# RGB.net
KiCad netlist of a schematic drawn in EAGLE
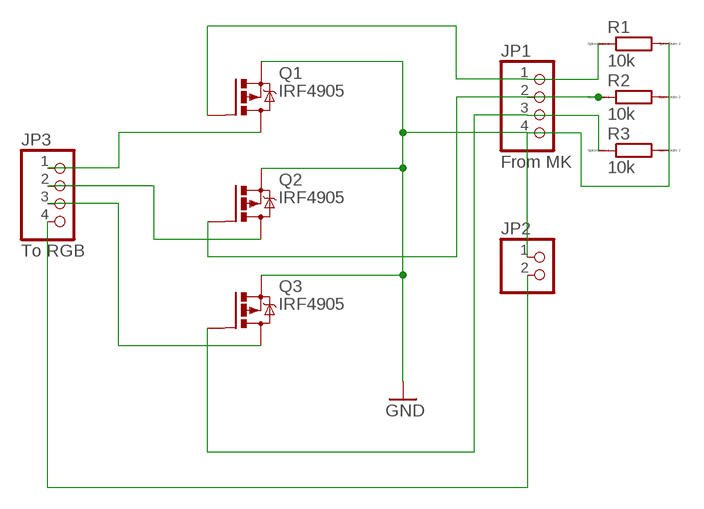
[diagram p0: schematic, sheet 1]

(export (version "E")
  (design (tool "Eeschema 10.0.6"))
  (components
    (comp (ref "JP1")
      (value "From MK")
      (footprint "eagle-import:1X04_90")
      (libsource (lib "eagle-import") (part "PINHD-1X4/90"))
    )
    (comp (ref "JP2")
      (value "PINHD-1X2/90")
      (footprint "eagle-import:1X02_90")
      (libsource (lib "eagle-import") (part "PINHD-1X2/90"))
    )
    (comp (ref "JP3")
      (value "To RGB")
      (footprint "eagle-import:1X04_90")
      (libsource (lib "eagle-import") (part "PINHD-1X4/90"))
    )
    (comp (ref "Q1")
      (value "IRF4905")
      (footprint "eagle-import:TO220BH")
      (libsource (lib "eagle-import") (part "IRF4905"))
    )
    (comp (ref "Q2")
      (value "IRF4905")
      (footprint "eagle-import:TO220BH")
      (libsource (lib "eagle-import") (part "IRF4905"))
    )
    (comp (ref "Q3")
      (value "IRF4905")
      (footprint "eagle-import:TO220BH")
      (libsource (lib "eagle-import") (part "IRF4905"))
    )
    (comp (ref "R1")
      (value "10k")
      (footprint "eagle-import:0207_10")
      (libsource (lib "eagle-import") (part "R0207/10"))
    )
    (comp (ref "R2")
      (value "10k")
      (footprint "eagle-import:0207_10")
      (libsource (lib "eagle-import") (part "R0207/10"))
    )
    (comp (ref "R3")
      (value "10k")
      (footprint "eagle-import:0207_10")
      (libsource (lib "eagle-import") (part "R0207/10"))
    )
  )
  (nets
    (net (code "1") (name "GND") (class "Default")
      (node (ref "JP1") (pin "4") (pinfunction "4_4") (pintype "passive"))
      (node (ref "JP2") (pin "1") (pinfunction "1_1") (pintype "passive"))
      (node (ref "Q1") (pin "S") (pinfunction "S_S") (pintype "passive"))
      (node (ref "Q2") (pin "S") (pinfunction "S_S") (pintype "passive"))
      (node (ref "Q3") (pin "S") (pinfunction "S_S") (pintype "passive"))
      (node (ref "R1") (pin "2") (pinfunction "2_2") (pintype "passive"))
      (node (ref "R2") (pin "2") (pinfunction "2_2") (pintype "passive"))
      (node (ref "R3") (pin "2") (pinfunction "2_2") (pintype "passive"))
    )
    (net (code "2") (name "Net-(JP1-Pad1)") (class "Default")
      (node (ref "JP1") (pin "1") (pinfunction "1_1") (pintype "passive"))
      (node (ref "Q1") (pin "G") (pinfunction "G_G") (pintype "passive"))
      (node (ref "R1") (pin "1") (pinfunction "1_1") (pintype "passive"))
    )
    (net (code "3") (name "Net-(JP1-Pad2)") (class "Default")
      (node (ref "JP1") (pin "2") (pinfunction "2_2") (pintype "passive"))
      (node (ref "Q2") (pin "G") (pinfunction "G_G") (pintype "passive"))
      (node (ref "R2") (pin "1") (pinfunction "1_1") (pintype "passive"))
    )
    (net (code "4") (name "Net-(JP1-Pad3)") (class "Default")
      (node (ref "JP1") (pin "3") (pinfunction "3_3") (pintype "passive"))
      (node (ref "Q3") (pin "G") (pinfunction "G_G") (pintype "passive"))
      (node (ref "R3") (pin "1") (pinfunction "1_1") (pintype "passive"))
    )
    (net (code "5") (name "Net-(JP2-Pad2)") (class "Default")
      (node (ref "JP2") (pin "2") (pinfunction "2_2") (pintype "passive"))
      (node (ref "JP3") (pin "4") (pinfunction "4_4") (pintype "passive"))
    )
    (net (code "6") (name "Net-(JP3-Pad1)") (class "Default")
      (node (ref "JP3") (pin "1") (pinfunction "1_1") (pintype "passive"))
      (node (ref "Q1") (pin "D") (pinfunction "D_D") (pintype "passive"))
    )
    (net (code "7") (name "Net-(JP3-Pad2)") (class "Default")
      (node (ref "JP3") (pin "2") (pinfunction "2_2") (pintype "passive"))
      (node (ref "Q2") (pin "D") (pinfunction "D_D") (pintype "passive"))
    )
    (net (code "8") (name "Net-(JP3-Pad3)") (class "Default")
      (node (ref "JP3") (pin "3") (pinfunction "3_3") (pintype "passive"))
      (node (ref "Q3") (pin "D") (pinfunction "D_D") (pintype "passive"))
    )
  )
)
